# HB.net
KiCad netlist of a schematic drawn in Altium Designer
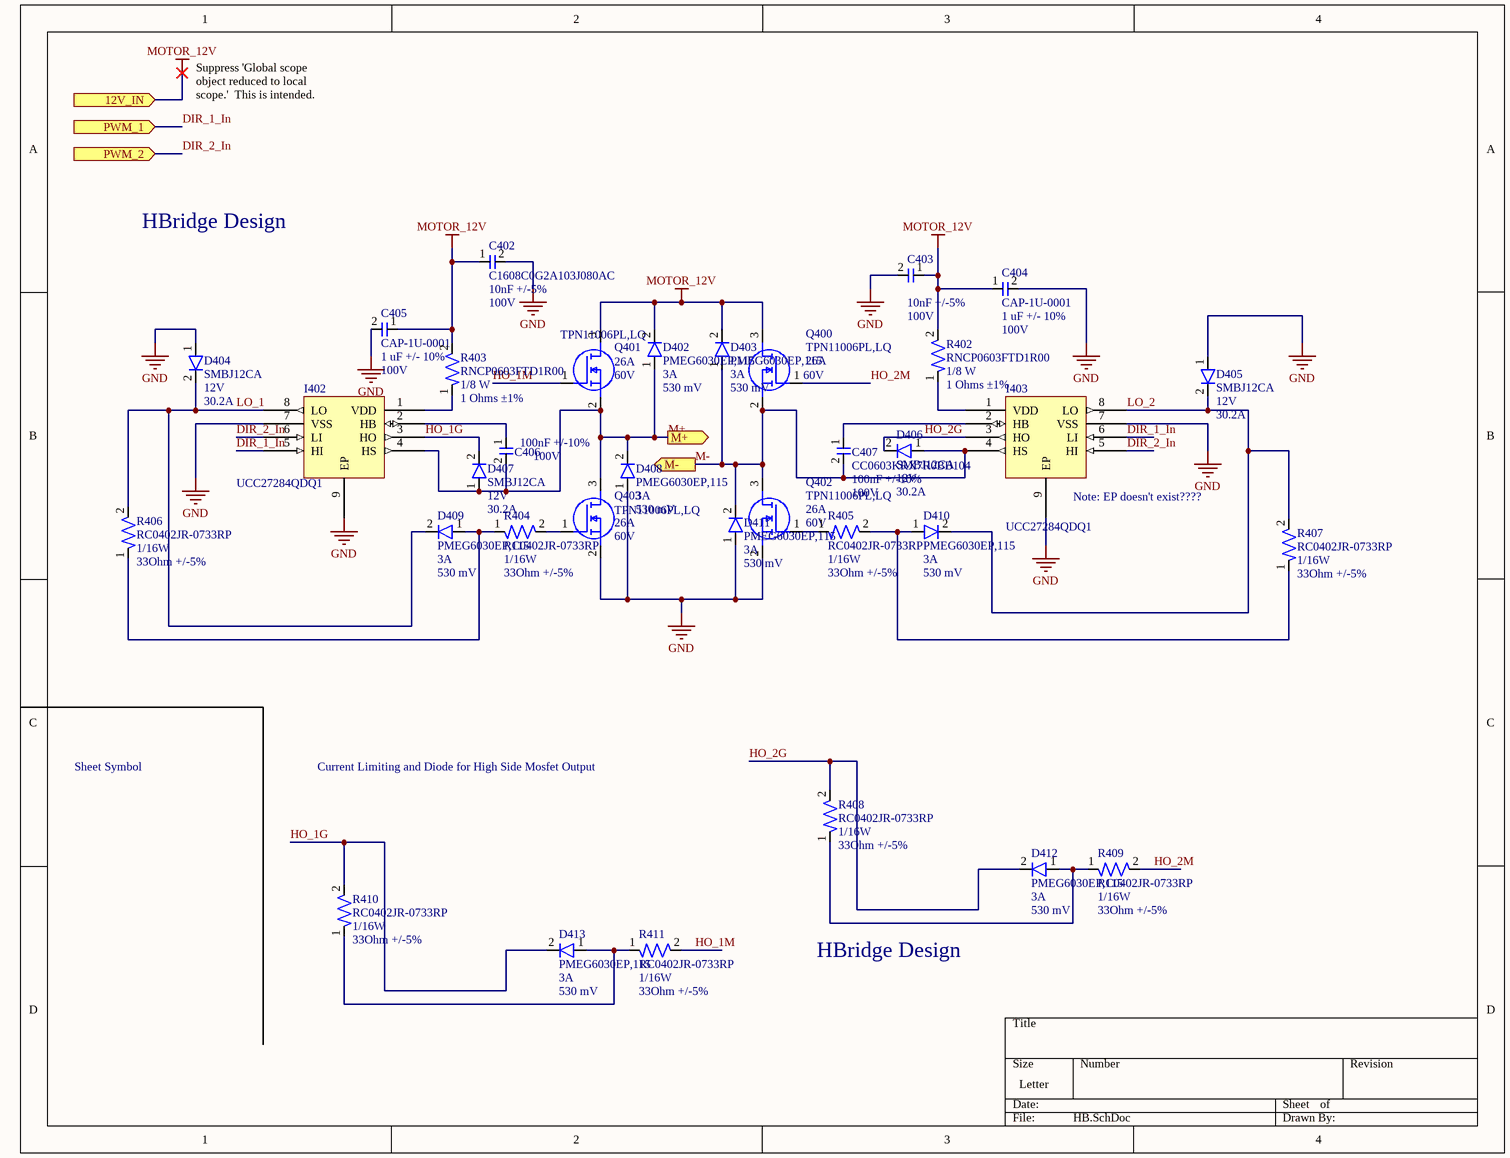
[diagram p0: HB.SchDoc]

(export (version "E")
  (design (tool "Eeschema 10.0.6"))
  (components
    (comp (ref "C402")
      (value "C1608C0G2A103J080AC")
      (footprint "MasterLib:CAP-0603")
      (description "CAP CER 10000PF 100V C0G 0603")
      (fields
        (field (name "MANUFACTURER") "TDK Corporation")
        (field (name "CAPACITANCE") "10nF +/-5%")
        (field (name "VOLTAGE RATING") "100V")
      )
      (libsource (lib "MasterLib") (part "CAP-10N-0002"))
    )
    (comp (ref "C403")
      (value "C1608C0G2A103J080AC")
      (footprint "MasterLib:CAP-0603")
      (description "CAP CER 10000PF 100V C0G 0603")
      (fields
        (field (name "MANUFACTURER") "TDK Corporation")
        (field (name "CAPACITANCE") "10nF +/-5%")
        (field (name "VOLTAGE RATING") "100V")
      )
      (libsource (lib "MasterLib") (part "CAP-10N-0002"))
    )
    (comp (ref "C404")
      (value "CAP-1U-0001")
      (footprint "MasterLib:CAP-1206 - duplicate")
      (description "1 µF ±10% 100V Ceramic Capacitor X7R 1206 (3216 Metric)")
      (fields (field (name "CAPACITANCE") "1 uF +/- 10%") (field (name "VOLTAGE") "100V"))
      (libsource (lib "MasterLib") (part "CAP-1U-0001"))
    )
    (comp (ref "C405")
      (value "CAP-1U-0001")
      (footprint "MasterLib:CAP-1206")
      (description "1 µF ±10% 100V Ceramic Capacitor X7R 1206 (3216 Metric)")
      (fields (field (name "CAPACITANCE") "1 uF +/- 10%") (field (name "VOLTAGE") "100V"))
      (libsource (lib "MasterLib") (part "CAP-1U-0001"))
    )
    (comp (ref "C406")
      (value "CC0603KRX7R0BB104")
      (footprint "MasterLib:CAP-0603")
      (description "CAP CER 0.1UF 100V X7R 0603")
      (fields
        (field (name "MANUFACTURER") "YAGEO")
        (field (name "CAPACITANCE") "100nF +/-10%")
        (field (name "VOLTAGE RATING") "100V")
      )
      (libsource (lib "MasterLib") (part "CAP-100N-0001"))
    )
    (comp (ref "C407")
      (value "CC0603KRX7R0BB104")
      (footprint "MasterLib:CAP-0603")
      (description "CAP CER 0.1UF 100V X7R 0603")
      (fields
        (field (name "MANUFACTURER") "YAGEO")
        (field (name "CAPACITANCE") "100nF +/-10%")
        (field (name "VOLTAGE RATING") "100V")
      )
      (libsource (lib "MasterLib") (part "CAP-100N-0001"))
    )
    (comp (ref "D402")
      (value "PMEG6030EP,115")
      (footprint "MasterLib:DIO-SOD128")
      (description "Diode Schottky 60 V 3A Surface Mount SOD-128/CFP5")
      (fields
        (field (name "MANUFACTURER") "Nexperia USA Inc.")
        (field (name "CURRENT RATING") "3A")
        (field (name "VF (VOLTAGE FORWARD)") "530 mV")
      )
      (libsource (lib "MasterLib") (part "DIO-0.53V-0001"))
    )
    (comp (ref "D403")
      (value "PMEG6030EP,115")
      (footprint "MasterLib:DIO-SOD128")
      (description "Diode Schottky 60 V 3A Surface Mount SOD-128/CFP5")
      (fields
        (field (name "MANUFACTURER") "Nexperia USA Inc.")
        (field (name "CURRENT RATING") "3A")
        (field (name "VF (VOLTAGE FORWARD)") "530 mV")
      )
      (libsource (lib "MasterLib") (part "DIO-0.53V-0001"))
    )
    (comp (ref "D404")
      (value "SMBJ12CA")
      (footprint "MasterLib:DO-214AA (SMBJ)")
      (description "19.9V Clamp 30.2A Ipp Tvs Diode Surface Mount DO-214AA (SMBJ)")
      (fields
        (field (name "MANUFACTURER") "Littlefuse Inc.")
        (field (name "STANDOFF VOLTAGE") "12V")
        (field (name "CURRENT RATING") "30.2A")
      )
      (libsource (lib "MasterLib") (part "DIO-19.9V-0001"))
    )
    (comp (ref "D405")
      (value "SMBJ12CA")
      (footprint "MasterLib:DO-214AA (SMBJ)")
      (description "19.9V Clamp 30.2A Ipp Tvs Diode Surface Mount DO-214AA (SMBJ)")
      (fields
        (field (name "MANUFACTURER") "Littlefuse Inc.")
        (field (name "STANDOFF VOLTAGE") "12V")
        (field (name "CURRENT RATING") "30.2A")
      )
      (libsource (lib "MasterLib") (part "DIO-19.9V-0001"))
    )
    (comp (ref "D406")
      (value "SMBJ12CA")
      (footprint "MasterLib:DO-214AA (SMBJ)")
      (description "19.9V Clamp 30.2A Ipp Tvs Diode Surface Mount DO-214AA (SMBJ)")
      (fields
        (field (name "MANUFACTURER") "Littlefuse Inc.")
        (field (name "STANDOFF VOLTAGE") "12V")
        (field (name "CURRENT RATING") "30.2A")
      )
      (libsource (lib "MasterLib") (part "DIO-19.9V-0001"))
    )
    (comp (ref "D407")
      (value "SMBJ12CA")
      (footprint "MasterLib:DO-214AA (SMBJ)")
      (description "19.9V Clamp 30.2A Ipp Tvs Diode Surface Mount DO-214AA (SMBJ)")
      (fields
        (field (name "MANUFACTURER") "Littlefuse Inc.")
        (field (name "STANDOFF VOLTAGE") "12V")
        (field (name "CURRENT RATING") "30.2A")
      )
      (libsource (lib "MasterLib") (part "DIO-19.9V-0001"))
    )
    (comp (ref "D408")
      (value "PMEG6030EP,115")
      (footprint "MasterLib:DIO-SOD128")
      (description "Diode Schottky 60 V 3A Surface Mount SOD-128/CFP5")
      (fields
        (field (name "MANUFACTURER") "Nexperia USA Inc.")
        (field (name "CURRENT RATING") "3A")
        (field (name "VF (VOLTAGE FORWARD)") "530 mV")
      )
      (libsource (lib "MasterLib") (part "DIO-0.53V-0001"))
    )
    (comp (ref "D409")
      (value "PMEG6030EP,115")
      (footprint "MasterLib:DIO-SOD128")
      (description "Diode Schottky 60 V 3A Surface Mount SOD-128/CFP5")
      (fields
        (field (name "MANUFACTURER") "Nexperia USA Inc.")
        (field (name "CURRENT RATING") "3A")
        (field (name "VF (VOLTAGE FORWARD)") "530 mV")
      )
      (libsource (lib "MasterLib") (part "DIO-0.53V-0001"))
    )
    (comp (ref "D410")
      (value "PMEG6030EP,115")
      (footprint "MasterLib:DIO-SOD128")
      (description "Diode Schottky 60 V 3A Surface Mount SOD-128/CFP5")
      (fields
        (field (name "MANUFACTURER") "Nexperia USA Inc.")
        (field (name "CURRENT RATING") "3A")
        (field (name "VF (VOLTAGE FORWARD)") "530 mV")
      )
      (libsource (lib "MasterLib") (part "DIO-0.53V-0001"))
    )
    (comp (ref "D411")
      (value "PMEG6030EP,115")
      (footprint "MasterLib:DIO-SOD128")
      (description "Diode Schottky 60 V 3A Surface Mount SOD-128/CFP5")
      (fields
        (field (name "MANUFACTURER") "Nexperia USA Inc.")
        (field (name "CURRENT RATING") "3A")
        (field (name "VF (VOLTAGE FORWARD)") "530 mV")
      )
      (libsource (lib "MasterLib") (part "DIO-0.53V-0001"))
    )
    (comp (ref "D412")
      (value "PMEG6030EP,115")
      (footprint "MasterLib:DIO-SOD128")
      (description "Diode Schottky 60 V 3A Surface Mount SOD-128/CFP5")
      (fields
        (field (name "MANUFACTURER") "Nexperia USA Inc.")
        (field (name "CURRENT RATING") "3A")
        (field (name "VF (VOLTAGE FORWARD)") "530 mV")
      )
      (libsource (lib "MasterLib") (part "DIO-0.53V-0001"))
    )
    (comp (ref "D413")
      (value "PMEG6030EP,115")
      (footprint "MasterLib:DIO-SOD128")
      (description "Diode Schottky 60 V 3A Surface Mount SOD-128/CFP5")
      (fields
        (field (name "MANUFACTURER") "Nexperia USA Inc.")
        (field (name "CURRENT RATING") "3A")
        (field (name "VF (VOLTAGE FORWARD)") "530 mV")
      )
      (libsource (lib "MasterLib") (part "DIO-0.53V-0001"))
    )
    (comp (ref "I402")
      (value "UCC27284QDQ1")
      (footprint "MasterLib:IC-BUCK-8SOIC")
      (fields (field (name "MANUFACTURER") "Texas Instruments"))
      (libsource (lib "") (part "IC-GDRV-0001_1"))
    )
    (comp (ref "I403")
      (value "UCC27284QDQ1")
      (footprint "MasterLib:IC-BUCK-8SOIC")
      (fields (field (name "MANUFACTURER") "Texas Instruments"))
      (libsource (lib "MasterLib") (part "IC-GDRV-0001"))
    )
    (comp (ref "Q400")
      (value "TPN11006PL,LQ")
      (footprint "MasterLib:NMOS-8TSON")
      (description "MOSFET N-CH 60V 200MA SOT23")
      (fields
        (field (name "MANUFACTURER") "Toshiba")
        (field (name "ID-CONTINUOUS") "26A")
        (field (name "VDS-MAX") "60V")
      )
      (libsource (lib "MasterLib") (part "NMOS-26A-0001"))
    )
    (comp (ref "Q401")
      (value "TPN11006PL,LQ")
      (footprint "MasterLib:NMOS-8TSON")
      (description "MOSFET N-CH 60V 200MA SOT23")
      (fields
        (field (name "MANUFACTURER") "Toshiba")
        (field (name "ID-CONTINUOUS") "26A")
        (field (name "VDS-MAX") "60V")
      )
      (libsource (lib "MasterLib") (part "NMOS-26A-0001"))
    )
    (comp (ref "Q402")
      (value "TPN11006PL,LQ")
      (footprint "MasterLib:NMOS-8TSON")
      (description "MOSFET N-CH 60V 200MA SOT23")
      (fields
        (field (name "MANUFACTURER") "Toshiba")
        (field (name "ID-CONTINUOUS") "26A")
        (field (name "VDS-MAX") "60V")
      )
      (libsource (lib "MasterLib") (part "NMOS-26A-0001"))
    )
    (comp (ref "Q403")
      (value "TPN11006PL,LQ")
      (footprint "MasterLib:NMOS-8TSON")
      (description "MOSFET N-CH 60V 200MA SOT23")
      (fields
        (field (name "MANUFACTURER") "Toshiba")
        (field (name "ID-CONTINUOUS") "26A")
        (field (name "VDS-MAX") "60V")
      )
      (libsource (lib "MasterLib") (part "NMOS-26A-0001"))
    )
    (comp (ref "R402")
      (value "RNCP0603FTD1R00")
      (footprint "MasterLib:RES-0603")
      (description "1 Ohms ±1% 0.125W, 1/8W Chip Resistor 0603 (1608 Metric) Anti-Sulfur Thin Film")
      (fields (field (name "POWER") "1/8 W") (field (name "RESISTANCE") "1 Ohms ±1%"))
      (libsource (lib "MasterLib") (part "RES-1-0001"))
    )
    (comp (ref "R403")
      (value "RNCP0603FTD1R00")
      (footprint "MasterLib:RES-0603")
      (description "1 Ohms ±1% 0.125W, 1/8W Chip Resistor 0603 (1608 Metric) Anti-Sulfur Thin Film")
      (fields (field (name "POWER") "1/8 W") (field (name "RESISTANCE") "1 Ohms ±1%"))
      (libsource (lib "MasterLib") (part "RES-1-0001"))
    )
    (comp (ref "R404")
      (value "RC0402JR-0733RP")
      (footprint "MasterLib:RES-0402")
      (description "RES SMD 33 OHM 5% 1/16W 0402")
      (fields
        (field (name "MANUFACTURER") "YAGEO")
        (field (name "POWER RATING") "1/16W")
        (field (name "RESISTANCE") "33Ohm +/-5%")
      )
      (libsource (lib "MasterLib") (part "RES-33-0001"))
    )
    (comp (ref "R405")
      (value "RC0402JR-0733RP")
      (footprint "MasterLib:RES-0402")
      (description "RES SMD 33 OHM 5% 1/16W 0402")
      (fields
        (field (name "MANUFACTURER") "YAGEO")
        (field (name "POWER RATING") "1/16W")
        (field (name "RESISTANCE") "33Ohm +/-5%")
      )
      (libsource (lib "MasterLib") (part "RES-33-0001"))
    )
    (comp (ref "R406")
      (value "RC0402JR-0733RP")
      (footprint "MasterLib:RES-0402")
      (description "RES SMD 33 OHM 5% 1/16W 0402")
      (fields
        (field (name "MANUFACTURER") "YAGEO")
        (field (name "POWER RATING") "1/16W")
        (field (name "RESISTANCE") "33Ohm +/-5%")
      )
      (libsource (lib "MasterLib") (part "RES-33-0001"))
    )
    (comp (ref "R407")
      (value "RC0402JR-0733RP")
      (footprint "MasterLib:RES-0402")
      (description "RES SMD 33 OHM 5% 1/16W 0402")
      (fields
        (field (name "MANUFACTURER") "YAGEO")
        (field (name "POWER RATING") "1/16W")
        (field (name "RESISTANCE") "33Ohm +/-5%")
      )
      (libsource (lib "MasterLib") (part "RES-33-0001"))
    )
    (comp (ref "R408")
      (value "RC0402JR-0733RP")
      (footprint "MasterLib:RES-0402")
      (description "RES SMD 33 OHM 5% 1/16W 0402")
      (fields
        (field (name "MANUFACTURER") "YAGEO")
        (field (name "POWER RATING") "1/16W")
        (field (name "RESISTANCE") "33Ohm +/-5%")
      )
      (libsource (lib "MasterLib") (part "RES-33-0001"))
    )
    (comp (ref "R409")
      (value "RC0402JR-0733RP")
      (footprint "MasterLib:RES-0402")
      (description "RES SMD 33 OHM 5% 1/16W 0402")
      (fields
        (field (name "MANUFACTURER") "YAGEO")
        (field (name "POWER RATING") "1/16W")
        (field (name "RESISTANCE") "33Ohm +/-5%")
      )
      (libsource (lib "MasterLib") (part "RES-33-0001"))
    )
    (comp (ref "R410")
      (value "RC0402JR-0733RP")
      (footprint "MasterLib:RES-0402")
      (description "RES SMD 33 OHM 5% 1/16W 0402")
      (fields
        (field (name "MANUFACTURER") "YAGEO")
        (field (name "POWER RATING") "1/16W")
        (field (name "RESISTANCE") "33Ohm +/-5%")
      )
      (libsource (lib "MasterLib") (part "RES-33-0001"))
    )
    (comp (ref "R411")
      (value "RC0402JR-0733RP")
      (footprint "MasterLib:RES-0402")
      (description "RES SMD 33 OHM 5% 1/16W 0402")
      (fields
        (field (name "MANUFACTURER") "YAGEO")
        (field (name "POWER RATING") "1/16W")
        (field (name "RESISTANCE") "33Ohm +/-5%")
      )
      (libsource (lib "MasterLib") (part "RES-33-0001"))
    )
  )
  (nets
    (net (code "1") (name "/DIR_1_In") (class "Default")
      (node (ref "I402") (pin "5") (pinfunction "HI_5") (pintype "input"))
      (node (ref "I403") (pin "6") (pinfunction "LI_6") (pintype "input"))
    )
    (net (code "2") (name "/DIR_2_In") (class "Default")
      (node (ref "I402") (pin "6") (pinfunction "LI_6") (pintype "input"))
      (node (ref "I403") (pin "5") (pinfunction "HI_5") (pintype "input"))
    )
    (net (code "3") (name "/HO_1G") (class "Default")
      (node (ref "D407") (pin "2") (pintype "passive"))
      (node (ref "D413") (pin "2") (pintype "passive"))
      (node (ref "I402") (pin "3") (pinfunction "HO_3") (pintype "output"))
      (node (ref "R410") (pin "2") (pinfunction "2_2") (pintype "passive"))
    )
    (net (code "4") (name "/HO_1M") (class "Default")
      (node (ref "Q401") (pin "1") (pinfunction "G_1") (pintype "passive"))
      (node (ref "R411") (pin "2") (pinfunction "2_2") (pintype "passive"))
    )
    (net (code "5") (name "/HO_2G") (class "Default")
      (node (ref "D406") (pin "2") (pintype "passive"))
      (node (ref "D412") (pin "2") (pintype "passive"))
      (node (ref "I403") (pin "3") (pinfunction "HO_3") (pintype "output"))
      (node (ref "R408") (pin "2") (pinfunction "2_2") (pintype "passive"))
    )
    (net (code "6") (name "/HO_2M") (class "Default")
      (node (ref "Q400") (pin "1") (pinfunction "G_1") (pintype "passive"))
      (node (ref "R409") (pin "2") (pinfunction "2_2") (pintype "passive"))
    )
    (net (code "7") (name "/LO_1") (class "Default")
      (node (ref "D404") (pin "2") (pintype "passive"))
      (node (ref "D409") (pin "2") (pintype "passive"))
      (node (ref "I402") (pin "8") (pinfunction "LO_8") (pintype "output"))
      (node (ref "R406") (pin "2") (pinfunction "2_2") (pintype "passive"))
    )
    (net (code "8") (name "/LO_2") (class "Default")
      (node (ref "D405") (pin "2") (pintype "passive"))
      (node (ref "D410") (pin "2") (pintype "passive"))
      (node (ref "I403") (pin "8") (pinfunction "LO_8") (pintype "output"))
      (node (ref "R407") (pin "2") (pinfunction "2_2") (pintype "passive"))
    )
    (net (code "9") (name "/M+") (class "Default")
      (node (ref "C406") (pin "2") (pinfunction "2_2") (pintype "passive"))
      (node (ref "D402") (pin "1") (pintype "passive"))
      (node (ref "D407") (pin "1") (pintype "passive"))
      (node (ref "D408") (pin "2") (pintype "passive"))
      (node (ref "I402") (pin "4") (pinfunction "HS_4") (pintype "output"))
      (node (ref "Q401") (pin "2") (pinfunction "S_2") (pintype "passive"))
      (node (ref "Q403") (pin "3") (pinfunction "D_3") (pintype "passive"))
    )
    (net (code "10") (name "/M-") (class "Default")
      (node (ref "C407") (pin "2") (pinfunction "2_2") (pintype "passive"))
      (node (ref "D403") (pin "1") (pintype "passive"))
      (node (ref "D406") (pin "1") (pintype "passive"))
      (node (ref "D411") (pin "2") (pintype "passive"))
      (node (ref "I403") (pin "4") (pinfunction "HS_4") (pintype "output"))
      (node (ref "Q400") (pin "2") (pinfunction "S_2") (pintype "passive"))
      (node (ref "Q402") (pin "3") (pinfunction "D_3") (pintype "passive"))
    )
    (net (code "11") (name "GND") (class "Default")
      (node (ref "C402") (pin "2") (pinfunction "2_2") (pintype "passive"))
      (node (ref "C403") (pin "2") (pinfunction "2_2") (pintype "passive"))
      (node (ref "C404") (pin "2") (pinfunction "2_2") (pintype "passive"))
      (node (ref "C405") (pin "2") (pinfunction "2_2") (pintype "passive"))
      (node (ref "D404") (pin "1") (pintype "passive"))
      (node (ref "D405") (pin "1") (pintype "passive"))
      (node (ref "D408") (pin "1") (pintype "passive"))
      (node (ref "D411") (pin "1") (pintype "passive"))
      (node (ref "I402") (pin "7") (pinfunction "VSS_7") (pintype "power_in"))
      (node (ref "I402") (pin "9") (pinfunction "EP_9") (pintype "power_in"))
      (node (ref "I403") (pin "7") (pinfunction "VSS_7") (pintype "power_in"))
      (node (ref "I403") (pin "9") (pinfunction "EP_9") (pintype "power_in"))
      (node (ref "Q402") (pin "2") (pinfunction "S_2") (pintype "passive"))
      (node (ref "Q403") (pin "2") (pinfunction "S_2") (pintype "passive"))
    )
    (net (code "12") (name "MOTOR_12V") (class "Default")
      (node (ref "C402") (pin "1") (pinfunction "1_1") (pintype "passive"))
      (node (ref "C403") (pin "1") (pinfunction "1_1") (pintype "passive"))
      (node (ref "C404") (pin "1") (pinfunction "1_1") (pintype "passive"))
      (node (ref "C405") (pin "1") (pinfunction "1_1") (pintype "passive"))
      (node (ref "D402") (pin "2") (pintype "passive"))
      (node (ref "D403") (pin "2") (pintype "passive"))
      (node (ref "Q400") (pin "3") (pinfunction "D_3") (pintype "passive"))
      (node (ref "Q401") (pin "3") (pinfunction "D_3") (pintype "passive"))
      (node (ref "R402") (pin "2") (pinfunction "2_2") (pintype "passive"))
      (node (ref "R403") (pin "2") (pinfunction "2_2") (pintype "passive"))
    )
    (net (code "13") (name "Net-(D409-Pad1)") (class "Default")
      (node (ref "D409") (pin "1") (pintype "passive"))
      (node (ref "R404") (pin "1") (pinfunction "1_1") (pintype "passive"))
      (node (ref "R406") (pin "1") (pinfunction "1_1") (pintype "passive"))
    )
    (net (code "14") (name "Net-(D410-Pad1)") (class "Default")
      (node (ref "D410") (pin "1") (pintype "passive"))
      (node (ref "R405") (pin "2") (pinfunction "2_2") (pintype "passive"))
      (node (ref "R407") (pin "1") (pinfunction "1_1") (pintype "passive"))
    )
    (net (code "15") (name "Net-(D412-Pad1)") (class "Default")
      (node (ref "D412") (pin "1") (pintype "passive"))
      (node (ref "R408") (pin "1") (pinfunction "1_1") (pintype "passive"))
      (node (ref "R409") (pin "1") (pinfunction "1_1") (pintype "passive"))
    )
    (net (code "16") (name "Net-(D413-Pad1)") (class "Default")
      (node (ref "D413") (pin "1") (pintype "passive"))
      (node (ref "R410") (pin "1") (pinfunction "1_1") (pintype "passive"))
      (node (ref "R411") (pin "1") (pinfunction "1_1") (pintype "passive"))
    )
    (net (code "17") (name "Net-(I402-HB)") (class "Default")
      (node (ref "C406") (pin "1") (pinfunction "1_1") (pintype "passive"))
      (node (ref "I402") (pin "2") (pinfunction "HB_2") (pintype "bidirectional"))
    )
    (net (code "18") (name "Net-(I402-VDD)") (class "Default")
      (node (ref "I402") (pin "1") (pinfunction "VDD_1") (pintype "power_in"))
      (node (ref "R403") (pin "1") (pinfunction "1_1") (pintype "passive"))
    )
    (net (code "19") (name "Net-(I403-HB)") (class "Default")
      (node (ref "C407") (pin "1") (pinfunction "1_1") (pintype "passive"))
      (node (ref "I403") (pin "2") (pinfunction "HB_2") (pintype "bidirectional"))
    )
    (net (code "20") (name "Net-(I403-VDD)") (class "Default")
      (node (ref "I403") (pin "1") (pinfunction "VDD_1") (pintype "power_in"))
      (node (ref "R402") (pin "1") (pinfunction "1_1") (pintype "passive"))
    )
    (net (code "21") (name "Net-(Q402-G)") (class "Default")
      (node (ref "Q402") (pin "1") (pinfunction "G_1") (pintype "passive"))
      (node (ref "R405") (pin "1") (pinfunction "1_1") (pintype "passive"))
    )
    (net (code "22") (name "Net-(Q403-G)") (class "Default")
      (node (ref "Q403") (pin "1") (pinfunction "G_1") (pintype "passive"))
      (node (ref "R404") (pin "2") (pinfunction "2_2") (pintype "passive"))
    )
  )
)
